# terminals.net
KiCad netlist of a schematic drawn in EAGLE
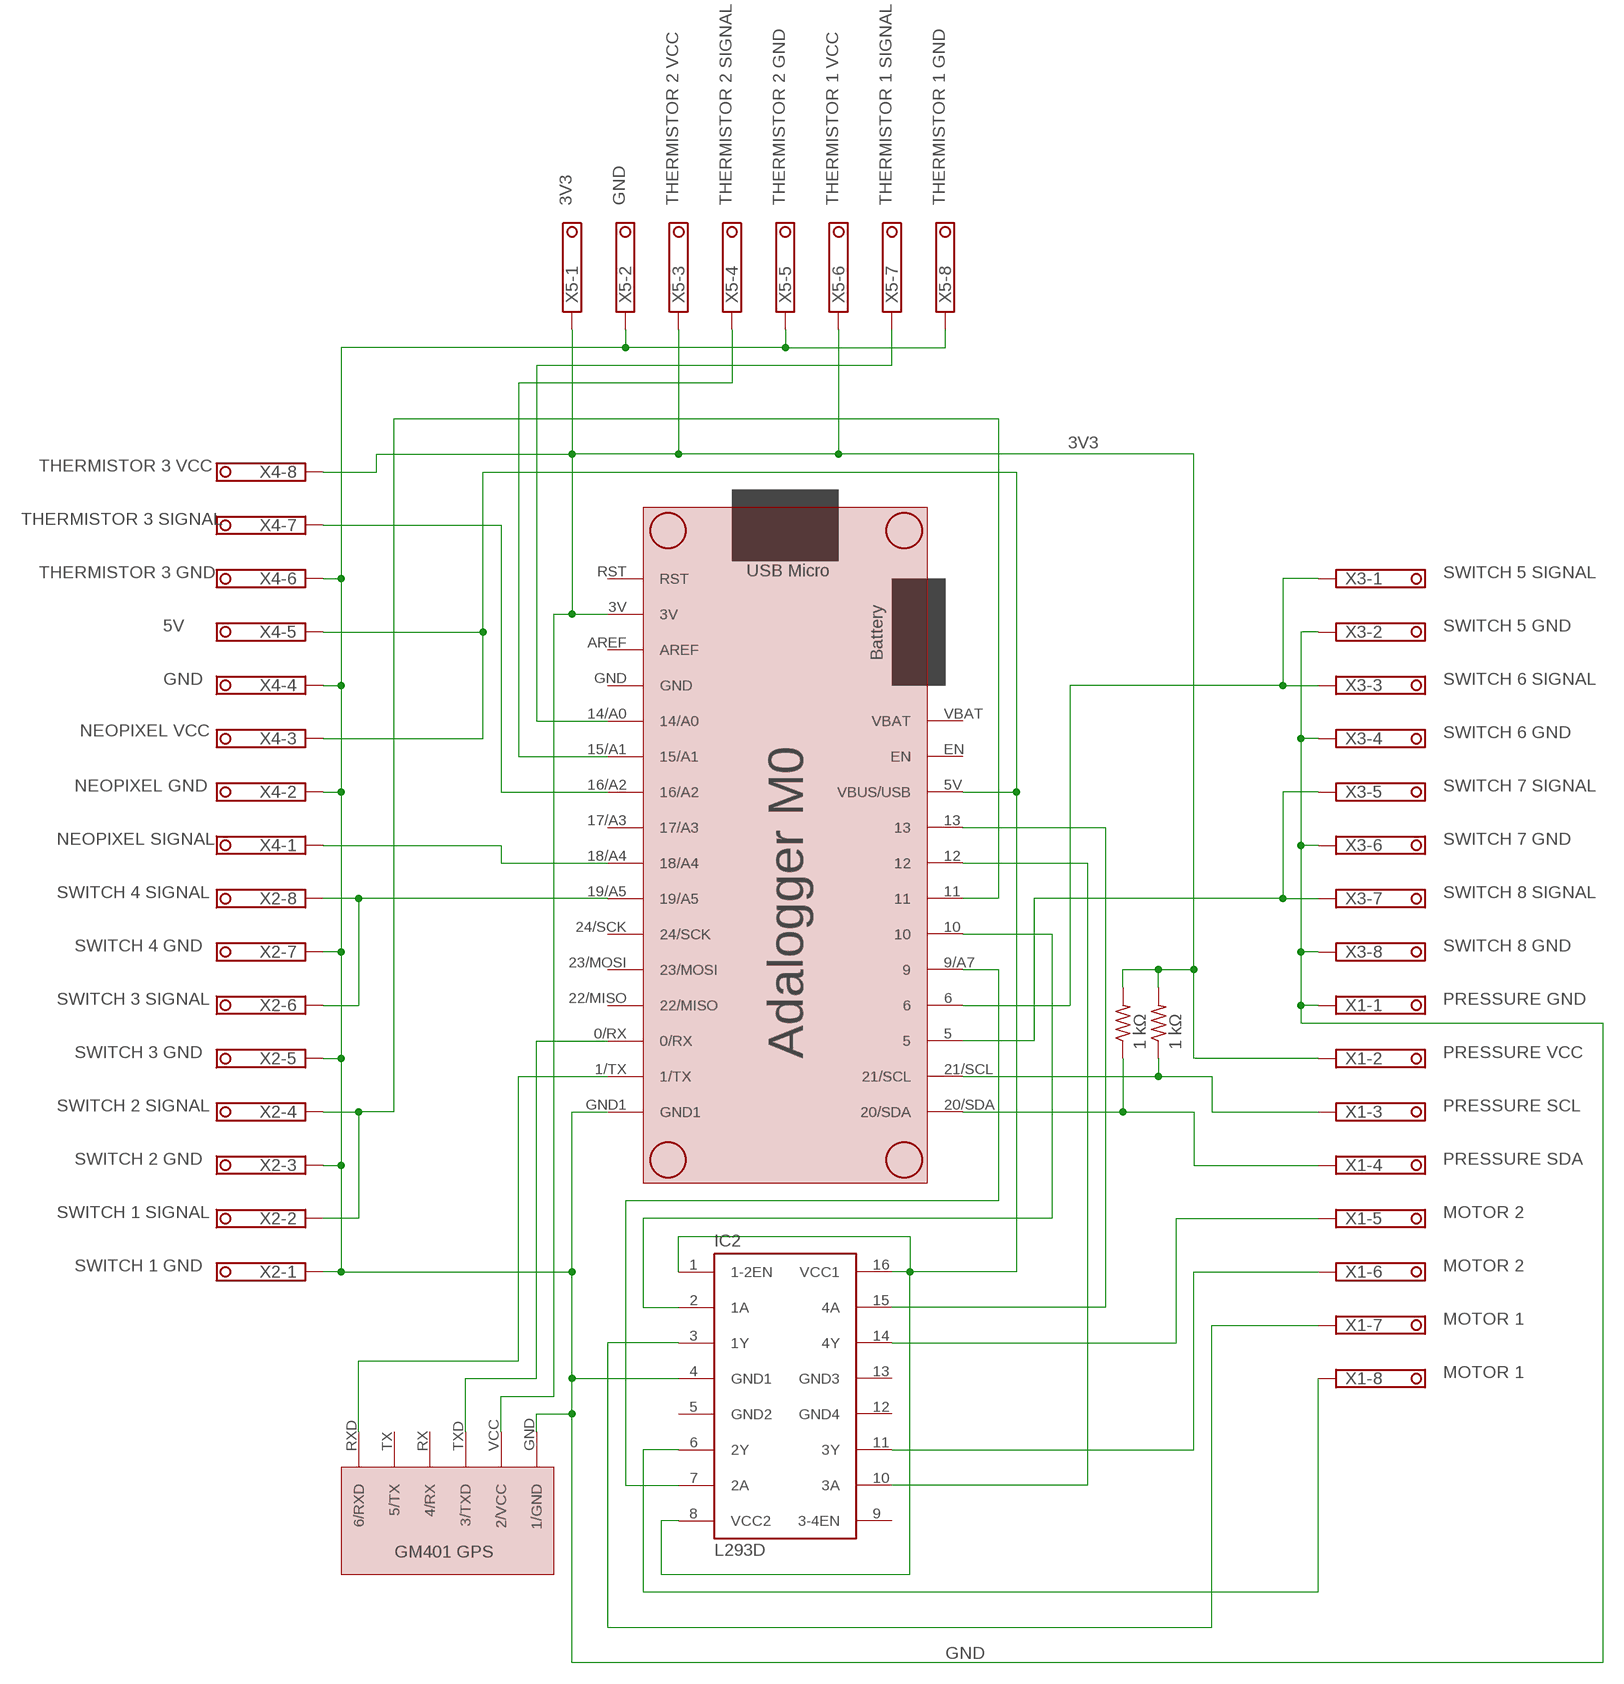
[diagram p0: schematic, sheet 1]

(export (version "E")
  (design (tool "Eeschema 10.0.6"))
  (components
    (comp (ref "IC2")
      (value "L293D")
      (footprint "eagle-import:DIL16")
      (libsource (lib "eagle-import") (part "L293D"))
    )
    (comp (ref "M0")
      (value "Adalogger M0")
      (footprint "eagle-import:BOARD")
      (libsource (lib "eagle-import") (part "ADALOGGER_M0"))
    )
    (comp (ref "R1")
      (value "1 kΩ")
      (footprint "eagle-import:0204_7")
      (libsource (lib "eagle-import") (part "R-US_0204/7"))
    )
    (comp (ref "R5")
      (value "1 kΩ")
      (footprint "eagle-import:0204_7")
      (libsource (lib "eagle-import") (part "R-US_0204/7"))
    )
    (comp (ref "U$1")
      (value "GPS")
      (footprint "eagle-import:GPS_BREAKOUT")
      (libsource (lib "eagle-import") (part "GPS"))
    )
    (comp (ref "X1")
      (value "1751303")
      (footprint "eagle-import:1751303")
      (libsource (lib "eagle-import") (part "1751303"))
    )
    (comp (ref "X2")
      (value "1751303")
      (footprint "eagle-import:1751303")
      (libsource (lib "eagle-import") (part "1751303"))
    )
    (comp (ref "X3")
      (value "1751303")
      (footprint "eagle-import:1751303")
      (libsource (lib "eagle-import") (part "1751303"))
    )
    (comp (ref "X4")
      (value "1751303")
      (footprint "eagle-import:1751303")
      (libsource (lib "eagle-import") (part "1751303"))
    )
    (comp (ref "X5")
      (value "1751303")
      (footprint "eagle-import:1751303")
      (libsource (lib "eagle-import") (part "1751303"))
    )
  )
  (nets
    (net (code "1") (name "/GND2") (class "Default")
      (node (ref "IC2") (pin "5") (pinfunction "GND2_5") (pintype "power_in"))
    )
    (net (code "2") (name "/GND3") (class "Default")
      (node (ref "IC2") (pin "13") (pinfunction "GND3_13") (pintype "power_in"))
    )
    (net (code "3") (name "/GND4") (class "Default")
      (node (ref "IC2") (pin "12") (pinfunction "GND4_12") (pintype "power_in"))
    )
    (net (code "4") (name "Net-(IC2-1-2EN)") (class "Default")
      (node (ref "IC2") (pin "1") (pinfunction "1-2EN_1") (pintype "input"))
      (node (ref "IC2") (pin "16") (pinfunction "VCC1_16") (pintype "power_in"))
      (node (ref "IC2") (pin "8") (pinfunction "VCC2_8") (pintype "power_in"))
      (node (ref "M0") (pin "5V") (pinfunction "VBUS/USB_5V") (pintype "bidirectional"))
      (node (ref "X4") (pin "3") (pinfunction "K_3") (pintype "passive"))
      (node (ref "X4") (pin "5") (pinfunction "K_5") (pintype "passive"))
    )
    (net (code "5") (name "Net-(IC2-1A)") (class "Default")
      (node (ref "IC2") (pin "2") (pinfunction "1A_2") (pintype "input"))
      (node (ref "M0") (pin "10") (pinfunction "10_10") (pintype "bidirectional"))
    )
    (net (code "6") (name "Net-(IC2-1Y)") (class "Default")
      (node (ref "IC2") (pin "3") (pinfunction "1Y_3") (pintype "output"))
      (node (ref "X1") (pin "7") (pinfunction "K_7") (pintype "passive"))
    )
    (net (code "7") (name "Net-(IC2-2A)") (class "Default")
      (node (ref "IC2") (pin "7") (pinfunction "2A_7") (pintype "input"))
      (node (ref "M0") (pin "9/A7") (pinfunction "9_9/A7") (pintype "bidirectional"))
    )
    (net (code "8") (name "Net-(IC2-2Y)") (class "Default")
      (node (ref "IC2") (pin "6") (pinfunction "2Y_6") (pintype "output"))
      (node (ref "X1") (pin "8") (pinfunction "K_8") (pintype "passive"))
    )
    (net (code "9") (name "Net-(IC2-3A)") (class "Default")
      (node (ref "IC2") (pin "10") (pinfunction "3A_10") (pintype "input"))
      (node (ref "M0") (pin "12") (pinfunction "12_12") (pintype "bidirectional"))
    )
    (net (code "10") (name "Net-(IC2-3Y)") (class "Default")
      (node (ref "IC2") (pin "11") (pinfunction "3Y_11") (pintype "output"))
      (node (ref "X1") (pin "6") (pinfunction "K_6") (pintype "passive"))
    )
    (net (code "11") (name "Net-(IC2-4A)") (class "Default")
      (node (ref "IC2") (pin "15") (pinfunction "4A_15") (pintype "input"))
      (node (ref "M0") (pin "13") (pinfunction "13_13") (pintype "bidirectional"))
    )
    (net (code "12") (name "Net-(IC2-4Y)") (class "Default")
      (node (ref "IC2") (pin "14") (pinfunction "4Y_14") (pintype "output"))
      (node (ref "X1") (pin "5") (pinfunction "K_5") (pintype "passive"))
    )
    (net (code "13") (name "Net-(IC2-GND1)") (class "Default")
      (node (ref "IC2") (pin "4") (pinfunction "GND1_4") (pintype "power_in"))
      (node (ref "M0") (pin "GND1") (pinfunction "GND1_GND1") (pintype "bidirectional"))
      (node (ref "U$1") (pin "GND") (pinfunction "1/GND_GND") (pintype "bidirectional"))
      (node (ref "X1") (pin "1") (pinfunction "K_1") (pintype "passive"))
      (node (ref "X2") (pin "1") (pinfunction "K_1") (pintype "passive"))
      (node (ref "X2") (pin "3") (pinfunction "K_3") (pintype "passive"))
      (node (ref "X2") (pin "5") (pinfunction "K_5") (pintype "passive"))
      (node (ref "X2") (pin "7") (pinfunction "K_7") (pintype "passive"))
      (node (ref "X3") (pin "2") (pinfunction "K_2") (pintype "passive"))
      (node (ref "X3") (pin "4") (pinfunction "K_4") (pintype "passive"))
      (node (ref "X3") (pin "6") (pinfunction "K_6") (pintype "passive"))
      (node (ref "X3") (pin "8") (pinfunction "K_8") (pintype "passive"))
      (node (ref "X4") (pin "2") (pinfunction "K_2") (pintype "passive"))
      (node (ref "X4") (pin "4") (pinfunction "K_4") (pintype "passive"))
      (node (ref "X4") (pin "6") (pinfunction "K_6") (pintype "passive"))
      (node (ref "X5") (pin "2") (pinfunction "K_2") (pintype "passive"))
      (node (ref "X5") (pin "5") (pinfunction "K_5") (pintype "passive"))
      (node (ref "X5") (pin "8") (pinfunction "K_8") (pintype "passive"))
    )
    (net (code "14") (name "Net-(U$1-2{slash}VCC)") (class "Default")
      (node (ref "M0") (pin "3V") (pinfunction "3V_3V") (pintype "bidirectional"))
      (node (ref "R1") (pin "2") (pinfunction "2_2") (pintype "passive"))
      (node (ref "R5") (pin "2") (pinfunction "2_2") (pintype "passive"))
      (node (ref "U$1") (pin "VCC") (pinfunction "2/VCC_VCC") (pintype "bidirectional"))
      (node (ref "X1") (pin "2") (pinfunction "K_2") (pintype "passive"))
      (node (ref "X4") (pin "8") (pinfunction "K_8") (pintype "passive"))
      (node (ref "X5") (pin "1") (pinfunction "K_1") (pintype "passive"))
      (node (ref "X5") (pin "3") (pinfunction "K_3") (pintype "passive"))
      (node (ref "X5") (pin "6") (pinfunction "K_6") (pintype "passive"))
    )
    (net (code "15") (name "Net-(U$1-3{slash}TXD)") (class "Default")
      (node (ref "M0") (pin "0/RX") (pinfunction "0/RX_0/RX") (pintype "bidirectional"))
      (node (ref "U$1") (pin "TXD") (pinfunction "3/TXD_TXD") (pintype "bidirectional"))
    )
    (net (code "16") (name "Net-(U$1-6{slash}RXD)") (class "Default")
      (node (ref "M0") (pin "1/TX") (pinfunction "1/TX_1/TX") (pintype "bidirectional"))
      (node (ref "U$1") (pin "RXD") (pinfunction "6/RXD_RXD") (pintype "bidirectional"))
    )
    (net (code "17") (name "Net-(X1C-K)") (class "Default")
      (node (ref "M0") (pin "21/SCL") (pinfunction "21/SCL_21/SCL") (pintype "bidirectional"))
      (node (ref "R5") (pin "1") (pinfunction "1_1") (pintype "passive"))
      (node (ref "X1") (pin "3") (pinfunction "K_3") (pintype "passive"))
    )
    (net (code "18") (name "Net-(X1D-K)") (class "Default")
      (node (ref "M0") (pin "20/SDA") (pinfunction "20/SDA_20/SDA") (pintype "bidirectional"))
      (node (ref "R1") (pin "1") (pinfunction "1_1") (pintype "passive"))
      (node (ref "X1") (pin "4") (pinfunction "K_4") (pintype "passive"))
    )
    (net (code "19") (name "Net-(X2B-K)") (class "Default")
      (node (ref "M0") (pin "11") (pinfunction "11_11") (pintype "bidirectional"))
      (node (ref "X2") (pin "2") (pinfunction "K_2") (pintype "passive"))
      (node (ref "X2") (pin "4") (pinfunction "K_4") (pintype "passive"))
    )
    (net (code "20") (name "Net-(X2F-K)") (class "Default")
      (node (ref "M0") (pin "19/A5") (pinfunction "19/A5_19/A5") (pintype "bidirectional"))
      (node (ref "X2") (pin "6") (pinfunction "K_6") (pintype "passive"))
      (node (ref "X2") (pin "8") (pinfunction "K_8") (pintype "passive"))
    )
    (net (code "21") (name "Net-(X3A-K)") (class "Default")
      (node (ref "M0") (pin "6") (pinfunction "6_6") (pintype "bidirectional"))
      (node (ref "X3") (pin "1") (pinfunction "K_1") (pintype "passive"))
      (node (ref "X3") (pin "3") (pinfunction "K_3") (pintype "passive"))
    )
    (net (code "22") (name "Net-(X3E-K)") (class "Default")
      (node (ref "M0") (pin "5") (pinfunction "5_5") (pintype "bidirectional"))
      (node (ref "X3") (pin "5") (pinfunction "K_5") (pintype "passive"))
      (node (ref "X3") (pin "7") (pinfunction "K_7") (pintype "passive"))
    )
    (net (code "23") (name "Net-(X4A-K)") (class "Default")
      (node (ref "M0") (pin "18/A4") (pinfunction "18/A4_18/A4") (pintype "bidirectional"))
      (node (ref "X4") (pin "1") (pinfunction "K_1") (pintype "passive"))
    )
    (net (code "24") (name "Net-(X4G-K)") (class "Default")
      (node (ref "M0") (pin "16/A2") (pinfunction "16/A2_16/A2") (pintype "bidirectional"))
      (node (ref "X4") (pin "7") (pinfunction "K_7") (pintype "passive"))
    )
    (net (code "25") (name "Net-(X5D-K)") (class "Default")
      (node (ref "M0") (pin "15/A1") (pinfunction "15/A1_15/A1") (pintype "bidirectional"))
      (node (ref "X5") (pin "4") (pinfunction "K_4") (pintype "passive"))
    )
    (net (code "26") (name "Net-(X5G-K)") (class "Default")
      (node (ref "M0") (pin "14/A0") (pinfunction "14/A0_14/A0") (pintype "bidirectional"))
      (node (ref "X5") (pin "7") (pinfunction "K_7") (pintype "passive"))
    )
    (net (code "27") (name "unconnected-(IC2-3-4EN-Pad9)") (class "Default")
      (node (ref "IC2") (pin "9") (pinfunction "3-4EN_9") (pintype "input"))
    )
    (net (code "28") (name "unconnected-(M0-Pad17{slash}A3)") (class "Default")
      (node (ref "M0") (pin "17/A3") (pinfunction "17/A3_17/A3") (pintype "bidirectional"))
    )
    (net (code "29") (name "unconnected-(M0-Pad22{slash}MISO)") (class "Default")
      (node (ref "M0") (pin "22/MISO") (pinfunction "22/MISO_22/MISO") (pintype "bidirectional"))
    )
    (net (code "30") (name "unconnected-(M0-Pad23{slash}MOSI)") (class "Default")
      (node (ref "M0") (pin "23/MOSI") (pinfunction "23/MOSI_23/MOSI") (pintype "bidirectional"))
    )
    (net (code "31") (name "unconnected-(M0-Pad24{slash}SCK)") (class "Default")
      (node (ref "M0") (pin "24/SCK") (pinfunction "24/SCK_24/SCK") (pintype "bidirectional"))
    )
    (net (code "32") (name "unconnected-(M0-PadAREF)") (class "Default")
      (node (ref "M0") (pin "AREF") (pinfunction "AREF_AREF") (pintype "bidirectional"))
    )
    (net (code "33") (name "unconnected-(M0-PadEN)") (class "Default")
      (node (ref "M0") (pin "EN") (pinfunction "EN_EN") (pintype "bidirectional"))
    )
    (net (code "34") (name "unconnected-(M0-PadGND)") (class "Default")
      (node (ref "M0") (pin "GND") (pinfunction "GND_GND") (pintype "bidirectional"))
    )
    (net (code "35") (name "unconnected-(M0-PadRST)") (class "Default")
      (node (ref "M0") (pin "RST") (pinfunction "RST_RST") (pintype "bidirectional"))
    )
    (net (code "36") (name "unconnected-(M0-PadVBAT)") (class "Default")
      (node (ref "M0") (pin "VBAT") (pinfunction "VBAT_VBAT") (pintype "bidirectional"))
    )
    (net (code "37") (name "unconnected-(U$1-4{slash}RX-PadRX)") (class "Default")
      (node (ref "U$1") (pin "RX") (pinfunction "4/RX_RX") (pintype "bidirectional"))
    )
    (net (code "38") (name "unconnected-(U$1-5{slash}TX-PadTX)") (class "Default")
      (node (ref "U$1") (pin "TX") (pinfunction "5/TX_TX") (pintype "bidirectional"))
    )
  )
)
